# RJ45_4ch_Output.net
KiCad netlist of a schematic drawn in EAGLE
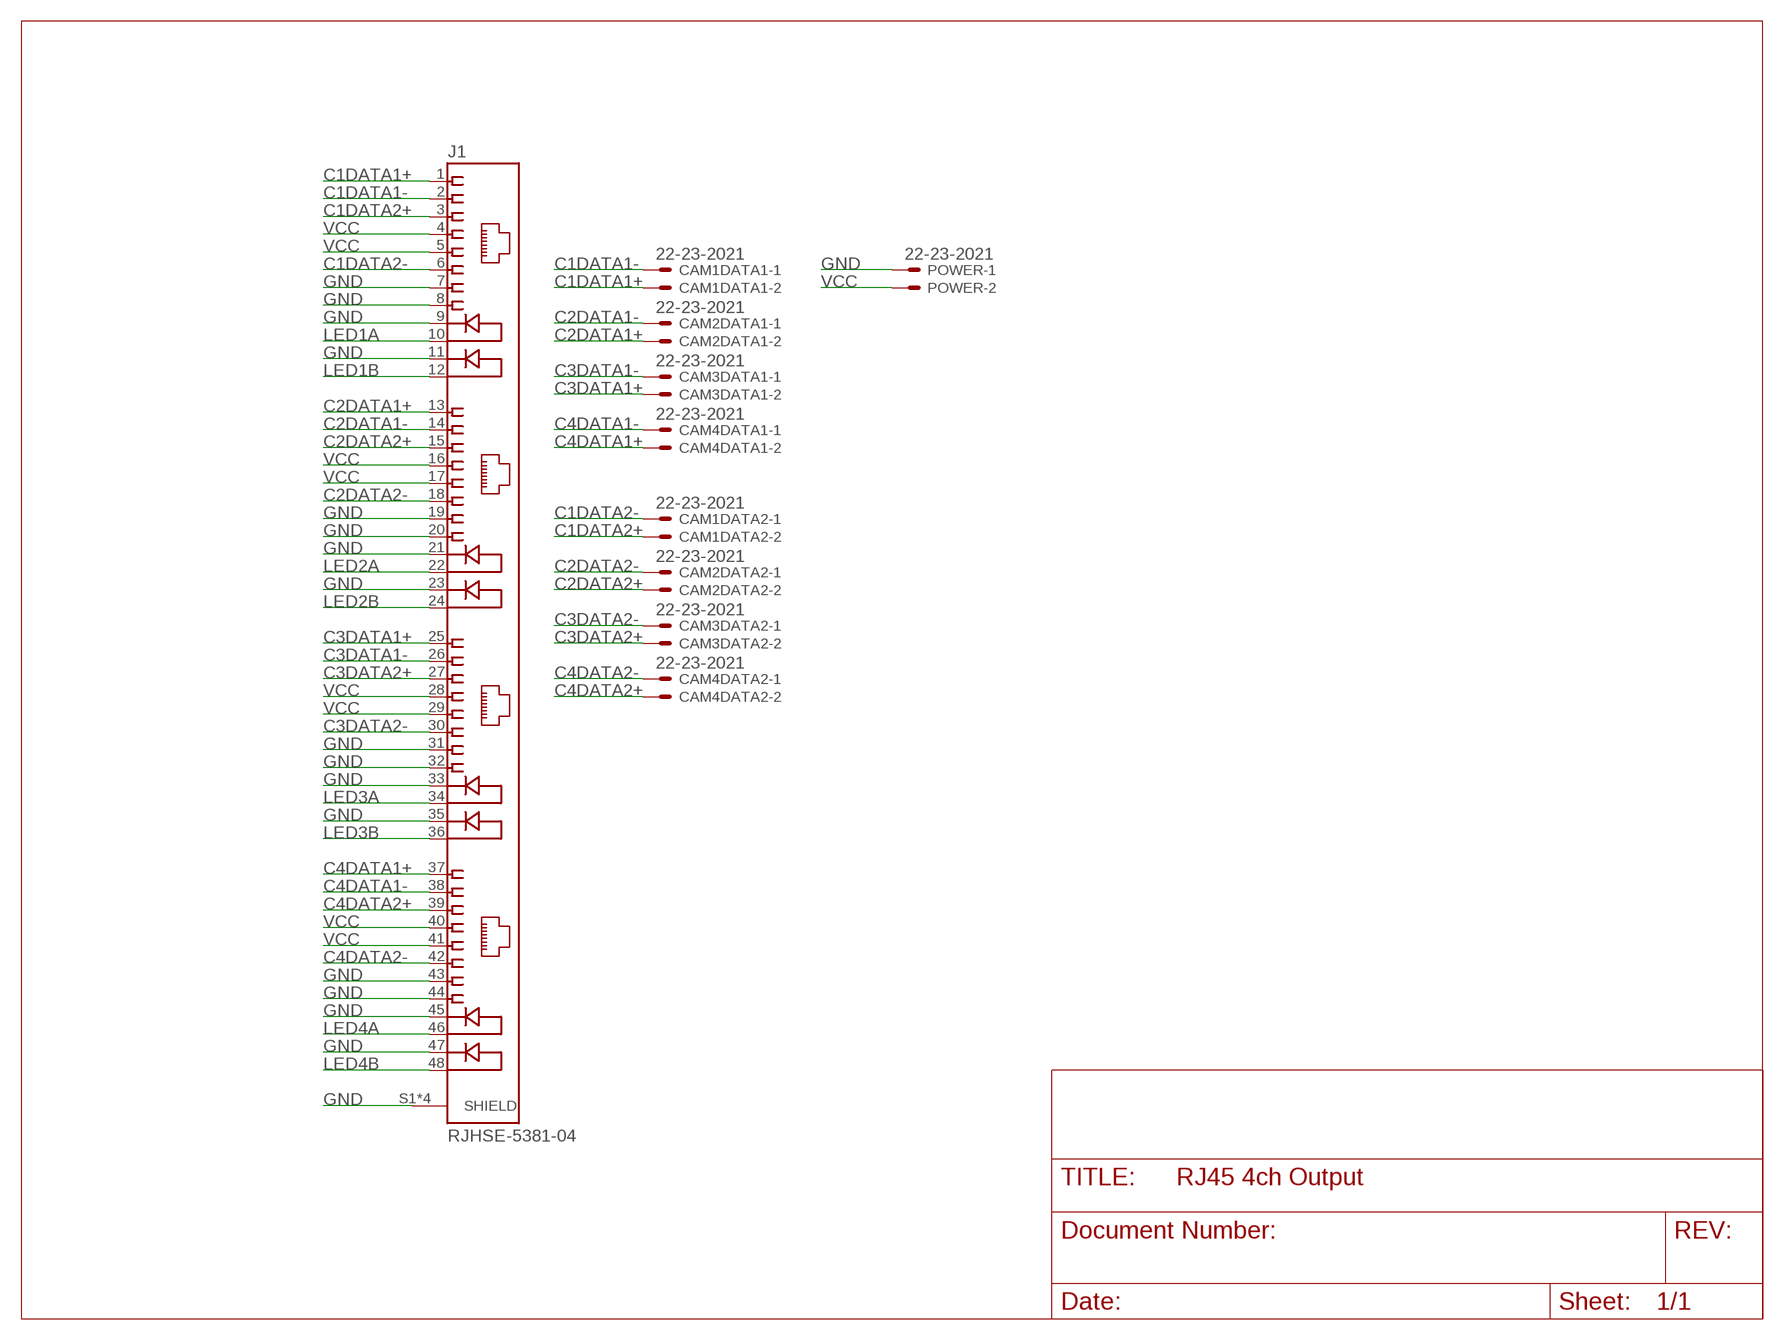
[diagram p0: schematic, sheet 1]

(export (version "E")
  (design (tool "Eeschema 10.0.6"))
  (components
    (comp (ref "CAM1DATA1")
      (value "22-23-2021")
      (footprint "eagle-import:22-23-2021")
      (fields (field (name "MF") "MOLEX"))
      (libsource (lib "eagle-import") (part "22-23-2021"))
    )
    (comp (ref "CAM1DATA2")
      (value "22-23-2021")
      (footprint "eagle-import:22-23-2021")
      (fields (field (name "MF") "MOLEX"))
      (libsource (lib "eagle-import") (part "22-23-2021"))
    )
    (comp (ref "CAM2DATA1")
      (value "22-23-2021")
      (footprint "eagle-import:22-23-2021")
      (fields (field (name "MF") "MOLEX"))
      (libsource (lib "eagle-import") (part "22-23-2021"))
    )
    (comp (ref "CAM2DATA2")
      (value "22-23-2021")
      (footprint "eagle-import:22-23-2021")
      (fields (field (name "MF") "MOLEX"))
      (libsource (lib "eagle-import") (part "22-23-2021"))
    )
    (comp (ref "CAM3DATA1")
      (value "22-23-2021")
      (footprint "eagle-import:22-23-2021")
      (fields (field (name "MF") "MOLEX"))
      (libsource (lib "eagle-import") (part "22-23-2021"))
    )
    (comp (ref "CAM3DATA2")
      (value "22-23-2021")
      (footprint "eagle-import:22-23-2021")
      (fields (field (name "MF") "MOLEX"))
      (libsource (lib "eagle-import") (part "22-23-2021"))
    )
    (comp (ref "CAM4DATA1")
      (value "22-23-2021")
      (footprint "eagle-import:22-23-2021")
      (fields (field (name "MF") "MOLEX"))
      (libsource (lib "eagle-import") (part "22-23-2021"))
    )
    (comp (ref "CAM4DATA2")
      (value "22-23-2021")
      (footprint "eagle-import:22-23-2021")
      (fields (field (name "MF") "MOLEX"))
      (libsource (lib "eagle-import") (part "22-23-2021"))
    )
    (comp (ref "J1")
      (value "RJHSE-5381-04")
      (footprint "eagle-import:AMPHENOL_RJHSE-5381-04")
      (fields (field (name "MF") "Amphenol ICC"))
      (libsource (lib "eagle-import") (part "RJHSE-5381-04"))
    )
    (comp (ref "POWER")
      (value "22-23-2021")
      (footprint "eagle-import:22-23-2021")
      (fields (field (name "MF") "MOLEX"))
      (libsource (lib "eagle-import") (part "22-23-2021"))
    )
  )
  (nets
    (net (code "1") (name "/C1DATA1+") (class "Default")
      (node (ref "CAM1DATA1") (pin "2") (pinfunction "S_2") (pintype "passive"))
      (node (ref "J1") (pin "1") (pinfunction "1_1") (pintype "passive"))
    )
    (net (code "2") (name "/C1DATA1-") (class "Default")
      (node (ref "CAM1DATA1") (pin "1") (pinfunction "S_1") (pintype "passive"))
      (node (ref "J1") (pin "2") (pinfunction "2_2") (pintype "passive"))
    )
    (net (code "3") (name "/C1DATA2+") (class "Default")
      (node (ref "CAM1DATA2") (pin "2") (pinfunction "S_2") (pintype "passive"))
      (node (ref "J1") (pin "3") (pinfunction "3_3") (pintype "passive"))
    )
    (net (code "4") (name "/C1DATA2-") (class "Default")
      (node (ref "CAM1DATA2") (pin "1") (pinfunction "S_1") (pintype "passive"))
      (node (ref "J1") (pin "6") (pinfunction "6_6") (pintype "passive"))
    )
    (net (code "5") (name "/C2DATA1+") (class "Default")
      (node (ref "CAM2DATA1") (pin "2") (pinfunction "S_2") (pintype "passive"))
      (node (ref "J1") (pin "13") (pinfunction "13_13") (pintype "passive"))
    )
    (net (code "6") (name "/C2DATA1-") (class "Default")
      (node (ref "CAM2DATA1") (pin "1") (pinfunction "S_1") (pintype "passive"))
      (node (ref "J1") (pin "14") (pinfunction "14_14") (pintype "passive"))
    )
    (net (code "7") (name "/C2DATA2+") (class "Default")
      (node (ref "CAM2DATA2") (pin "2") (pinfunction "S_2") (pintype "passive"))
      (node (ref "J1") (pin "15") (pinfunction "15_15") (pintype "passive"))
    )
    (net (code "8") (name "/C2DATA2-") (class "Default")
      (node (ref "CAM2DATA2") (pin "1") (pinfunction "S_1") (pintype "passive"))
      (node (ref "J1") (pin "18") (pinfunction "18_18") (pintype "passive"))
    )
    (net (code "9") (name "/C3DATA1+") (class "Default")
      (node (ref "CAM3DATA1") (pin "2") (pinfunction "S_2") (pintype "passive"))
      (node (ref "J1") (pin "25") (pinfunction "25_25") (pintype "passive"))
    )
    (net (code "10") (name "/C3DATA1-") (class "Default")
      (node (ref "CAM3DATA1") (pin "1") (pinfunction "S_1") (pintype "passive"))
      (node (ref "J1") (pin "26") (pinfunction "26_26") (pintype "passive"))
    )
    (net (code "11") (name "/C3DATA2+") (class "Default")
      (node (ref "CAM3DATA2") (pin "2") (pinfunction "S_2") (pintype "passive"))
      (node (ref "J1") (pin "27") (pinfunction "27_27") (pintype "passive"))
    )
    (net (code "12") (name "/C3DATA2-") (class "Default")
      (node (ref "CAM3DATA2") (pin "1") (pinfunction "S_1") (pintype "passive"))
      (node (ref "J1") (pin "30") (pinfunction "30_30") (pintype "passive"))
    )
    (net (code "13") (name "/C4DATA1+") (class "Default")
      (node (ref "CAM4DATA1") (pin "2") (pinfunction "S_2") (pintype "passive"))
      (node (ref "J1") (pin "37") (pinfunction "37_37") (pintype "passive"))
    )
    (net (code "14") (name "/C4DATA1-") (class "Default")
      (node (ref "CAM4DATA1") (pin "1") (pinfunction "S_1") (pintype "passive"))
      (node (ref "J1") (pin "38") (pinfunction "38_38") (pintype "passive"))
    )
    (net (code "15") (name "/C4DATA2+") (class "Default")
      (node (ref "CAM4DATA2") (pin "2") (pinfunction "S_2") (pintype "passive"))
      (node (ref "J1") (pin "39") (pinfunction "39_39") (pintype "passive"))
    )
    (net (code "16") (name "/C4DATA2-") (class "Default")
      (node (ref "CAM4DATA2") (pin "1") (pinfunction "S_1") (pintype "passive"))
      (node (ref "J1") (pin "42") (pinfunction "42_42") (pintype "passive"))
    )
    (net (code "17") (name "/GND") (class "Default")
      (node (ref "J1") (pin "11") (pinfunction "11_11") (pintype "passive"))
      (node (ref "J1") (pin "19") (pinfunction "19_19") (pintype "passive"))
      (node (ref "J1") (pin "20") (pinfunction "20_20") (pintype "passive"))
      (node (ref "J1") (pin "21") (pinfunction "21_21") (pintype "passive"))
      (node (ref "J1") (pin "23") (pinfunction "23_23") (pintype "passive"))
      (node (ref "J1") (pin "31") (pinfunction "31_31") (pintype "passive"))
      (node (ref "J1") (pin "32") (pinfunction "32_32") (pintype "passive"))
      (node (ref "J1") (pin "33") (pinfunction "33_33") (pintype "passive"))
      (node (ref "J1") (pin "35") (pinfunction "35_35") (pintype "passive"))
      (node (ref "J1") (pin "43") (pinfunction "43_43") (pintype "passive"))
      (node (ref "J1") (pin "44") (pinfunction "44_44") (pintype "passive"))
      (node (ref "J1") (pin "45") (pinfunction "45_45") (pintype "passive"))
      (node (ref "J1") (pin "47") (pinfunction "47_47") (pintype "passive"))
      (node (ref "J1") (pin "7") (pinfunction "7_7") (pintype "passive"))
      (node (ref "J1") (pin "8") (pinfunction "8_8") (pintype "passive"))
      (node (ref "J1") (pin "9") (pinfunction "9_9") (pintype "passive"))
      (node (ref "J1") (pin "S1") (pinfunction "SHIELD_S1") (pintype "passive"))
      (node (ref "J1") (pin "S2") (pinfunction "SHIELD_S2") (pintype "passive"))
      (node (ref "J1") (pin "S3") (pinfunction "SHIELD_S3") (pintype "passive"))
      (node (ref "J1") (pin "S4") (pinfunction "SHIELD_S4") (pintype "passive"))
      (node (ref "POWER") (pin "1") (pinfunction "S_1") (pintype "passive"))
    )
    (net (code "18") (name "/LED1A") (class "Default")
      (node (ref "J1") (pin "10") (pinfunction "10_10") (pintype "passive"))
    )
    (net (code "19") (name "/LED1B") (class "Default")
      (node (ref "J1") (pin "12") (pinfunction "12_12") (pintype "passive"))
    )
    (net (code "20") (name "/LED2A") (class "Default")
      (node (ref "J1") (pin "22") (pinfunction "22_22") (pintype "passive"))
    )
    (net (code "21") (name "/LED2B") (class "Default")
      (node (ref "J1") (pin "24") (pinfunction "24_24") (pintype "passive"))
    )
    (net (code "22") (name "/LED3A") (class "Default")
      (node (ref "J1") (pin "34") (pinfunction "34_34") (pintype "passive"))
    )
    (net (code "23") (name "/LED3B") (class "Default")
      (node (ref "J1") (pin "36") (pinfunction "36_36") (pintype "passive"))
    )
    (net (code "24") (name "/LED4A") (class "Default")
      (node (ref "J1") (pin "46") (pinfunction "46_46") (pintype "passive"))
    )
    (net (code "25") (name "/LED4B") (class "Default")
      (node (ref "J1") (pin "48") (pinfunction "48_48") (pintype "passive"))
    )
    (net (code "26") (name "/VCC") (class "Default")
      (node (ref "J1") (pin "16") (pinfunction "16_16") (pintype "passive"))
      (node (ref "J1") (pin "17") (pinfunction "17_17") (pintype "passive"))
      (node (ref "J1") (pin "28") (pinfunction "28_28") (pintype "passive"))
      (node (ref "J1") (pin "29") (pinfunction "29_29") (pintype "passive"))
      (node (ref "J1") (pin "4") (pinfunction "4_4") (pintype "passive"))
      (node (ref "J1") (pin "40") (pinfunction "40_40") (pintype "passive"))
      (node (ref "J1") (pin "41") (pinfunction "41_41") (pintype "passive"))
      (node (ref "J1") (pin "5") (pinfunction "5_5") (pintype "passive"))
      (node (ref "POWER") (pin "2") (pinfunction "S_2") (pintype "passive"))
    )
  )
)
